# Source_OPV_ADC.net
KiCad netlist of a schematic drawn in Altium Designer
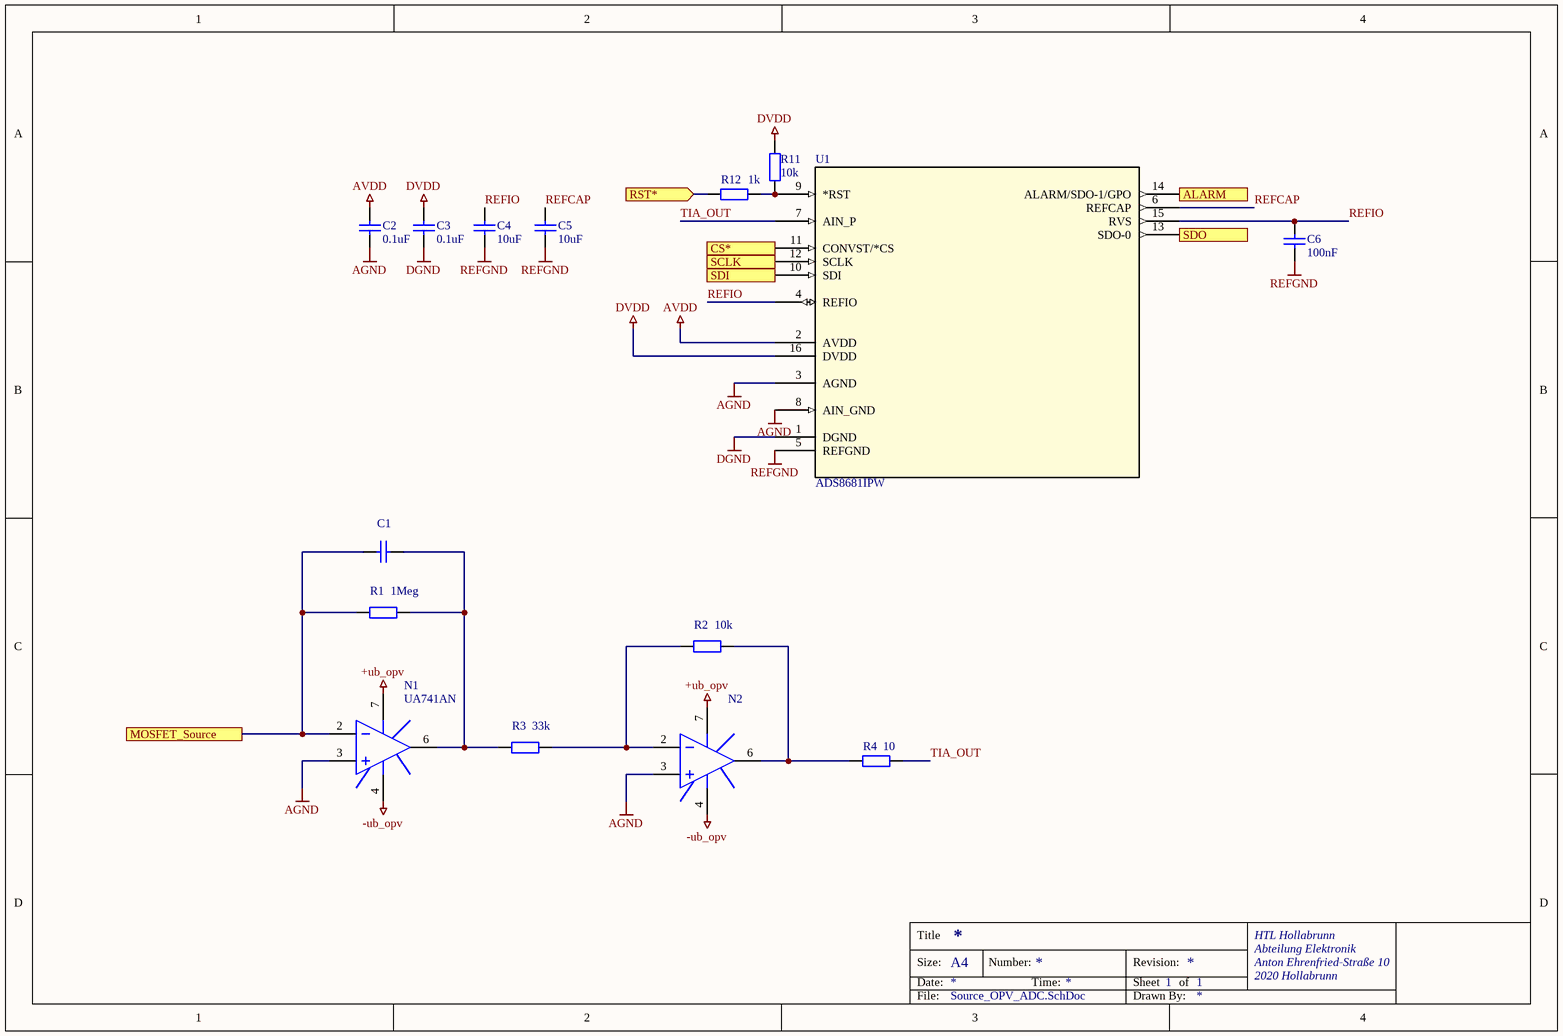
[diagram p0: Source_OPV_ADC.SchDoc]

(export (version "E")
  (design (tool "Eeschema 10.0.6"))
  (components
    (comp (ref "C1")
      (value "100nF")
      (footprint "C1206-KUE")
      (description "Capacitor")
      (fields (field (name "MANUFACTURER") "Kemet") (field (name "PUBLISHER") "Altium Limited"))
      (libsource (lib "ExtrapartsKUE_V01") (part "Capacitor"))
    )
    (comp (ref "C2")
      (value "0.1uF")
      (footprint "C1206-KUE")
      (description "Capacitor")
      (fields (field (name "MANUFACTURER") "Kemet") (field (name "PUBLISHER") "Altium Limited"))
      (libsource (lib "ExtrapartsKUE_V01") (part "Capacitor"))
    )
    (comp (ref "C3")
      (value "0.1uF")
      (footprint "C1206-KUE")
      (description "Capacitor")
      (fields (field (name "MANUFACTURER") "Kemet") (field (name "PUBLISHER") "Altium Limited"))
      (libsource (lib "ExtrapartsKUE_V01") (part "Capacitor"))
    )
    (comp (ref "C4")
      (value "10uF")
      (footprint "C1206-KUE")
      (description "Capacitor")
      (fields (field (name "MANUFACTURER") "Kemet") (field (name "PUBLISHER") "Altium Limited"))
      (libsource (lib "ExtrapartsKUE_V01") (part "Capacitor"))
    )
    (comp (ref "C5")
      (value "10uF")
      (footprint "C1206-KUE")
      (description "Capacitor")
      (fields (field (name "MANUFACTURER") "Kemet") (field (name "PUBLISHER") "Altium Limited"))
      (libsource (lib "ExtrapartsKUE_V01") (part "Capacitor"))
    )
    (comp (ref "C6")
      (value "100nF")
      (footprint "C1206-KUE")
      (description "Capacitor")
      (fields (field (name "MANUFACTURER") "Kemet") (field (name "PUBLISHER") "Altium Limited"))
      (libsource (lib "ExtrapartsKUE_V01") (part "Capacitor"))
    )
    (comp (ref "N1")
      (value "UA741AN")
      (footprint "DIP8")
      (description "General-Purpose Single Operational Amplifier")
      (fields (field (name "PUBLISHER") "Altium Limited"))
      (libsource (lib "ST Operational Amplifier") (part "UA741AN"))
    )
    (comp (ref "N2")
      (value "UA741AN")
      (footprint "DIP8")
      (description "General-Purpose Single Operational Amplifier")
      (fields (field (name "PUBLISHER") "Altium Limited"))
      (libsource (lib "ST Operational Amplifier") (part "UA741AN"))
    )
    (comp (ref "R1")
      (value "1Meg")
      (footprint "C1206-KUE")
      (description "Resistor SMD")
      (fields (field (name "MANUFACTURER") "AVX") (field (name "PUBLISHER") "Altium Limited"))
      (libsource (lib "") (part "ResistorSMD_1"))
    )
    (comp (ref "R2")
      (value "10k")
      (footprint "C1206-KUE")
      (description "Resistor SMD")
      (fields (field (name "MANUFACTURER") "AVX") (field (name "PUBLISHER") "Altium Limited"))
      (libsource (lib "") (part "ResistorSMD_1"))
    )
    (comp (ref "R3")
      (value "33k")
      (footprint "C1206-KUE")
      (description "Resistor SMD")
      (fields (field (name "MANUFACTURER") "AVX") (field (name "PUBLISHER") "Altium Limited"))
      (libsource (lib "") (part "ResistorSMD_1"))
    )
    (comp (ref "R4")
      (value "10")
      (footprint "C1206-KUE")
      (description "Resistor SMD")
      (fields (field (name "MANUFACTURER") "AVX") (field (name "PUBLISHER") "Altium Limited"))
      (libsource (lib "") (part "ResistorSMD_1"))
    )
    (comp (ref "R11")
      (value "10k")
      (footprint "C1206-KUE")
      (description "Resistor SMD")
      (fields (field (name "MANUFACTURER") "AVX") (field (name "PUBLISHER") "Altium Limited"))
      (libsource (lib "") (part "ResistorSMD_2"))
    )
    (comp (ref "R12")
      (value "1k")
      (footprint "C1206-KUE")
      (description "Resistor SMD")
      (fields (field (name "MANUFACTURER") "AVX") (field (name "PUBLISHER") "Altium Limited"))
      (libsource (lib "ExtrapartsKUE_V01") (part "ResistorSMD"))
    )
    (comp (ref "U1")
      (value "ADS8681IPW")
      (footprint "PW16_TEX")
      (fields (field (name "COPYRIGHT") "Copyright (C) 2025 Ultra Librarian. All rights reserved."))
      (libsource (lib "ADS8681IPW") (part "ADS8681IPW"))
    )
  )
  (nets
    (net (code "1") (name "+ub_opv") (class "Default")
      (node (ref "N1") (pin "7") (pinfunction "V+_7") (pintype "passive"))
      (node (ref "N2") (pin "7") (pinfunction "V+_7") (pintype "passive"))
    )
    (net (code "2") (name "-ub_opv") (class "Default")
      (node (ref "N1") (pin "4") (pinfunction "V-_4") (pintype "passive"))
      (node (ref "N2") (pin "4") (pinfunction "V-_4") (pintype "passive"))
    )
    (net (code "3") (name "/ALARM") (class "Default")
      (node (ref "U1") (pin "14") (pinfunction "ALARM/SDO-1/GPO_14") (pintype "output"))
    )
    (net (code "4") (name "/CS*") (class "Default")
      (node (ref "U1") (pin "11") (pinfunction "CONVST/*CS_11") (pintype "input"))
    )
    (net (code "5") (name "/MOSFET_Source") (class "Default")
      (node (ref "C1") (pin "1") (pinfunction "1_1") (pintype "passive"))
      (node (ref "N1") (pin "2") (pinfunction "IN-_2") (pintype "passive"))
      (node (ref "R1") (pin "2") (pinfunction "2_2") (pintype "passive"))
    )
    (net (code "6") (name "/REFCAP") (class "Default")
      (node (ref "C5") (pin "2") (pinfunction "2_2") (pintype "passive"))
      (node (ref "U1") (pin "6") (pinfunction "REFCAP_6") (pintype "output"))
    )
    (net (code "7") (name "/REFIO") (class "Default")
      (node (ref "C4") (pin "2") (pinfunction "2_2") (pintype "passive"))
      (node (ref "C6") (pin "2") (pinfunction "2_2") (pintype "passive"))
      (node (ref "U1") (pin "15") (pinfunction "RVS_15") (pintype "output"))
      (node (ref "U1") (pin "4") (pinfunction "REFIO_4") (pintype "bidirectional"))
    )
    (net (code "8") (name "/RST*") (class "Default")
      (node (ref "R12") (pin "1") (pinfunction "1_1") (pintype "passive"))
    )
    (net (code "9") (name "/SCLK") (class "Default")
      (node (ref "U1") (pin "12") (pinfunction "SCLK_12") (pintype "input"))
    )
    (net (code "10") (name "/SDI") (class "Default")
      (node (ref "U1") (pin "10") (pinfunction "SDI_10") (pintype "input"))
    )
    (net (code "11") (name "/SDO") (class "Default")
      (node (ref "U1") (pin "13") (pinfunction "SDO-0_13") (pintype "output"))
    )
    (net (code "12") (name "/TIA_OUT") (class "Default")
      (node (ref "R4") (pin "1") (pinfunction "1_1") (pintype "passive"))
      (node (ref "U1") (pin "7") (pinfunction "AIN_P_7") (pintype "input"))
    )
    (net (code "13") (name "AGND") (class "Default")
      (node (ref "C2") (pin "1") (pinfunction "1_1") (pintype "passive"))
      (node (ref "N1") (pin "3") (pinfunction "IN+_3") (pintype "passive"))
      (node (ref "N2") (pin "3") (pinfunction "IN+_3") (pintype "passive"))
      (node (ref "U1") (pin "3") (pinfunction "AGND_3") (pintype "power_in"))
      (node (ref "U1") (pin "8") (pinfunction "AIN_GND_8") (pintype "input"))
    )
    (net (code "14") (name "AVDD") (class "Default")
      (node (ref "C2") (pin "2") (pinfunction "2_2") (pintype "passive"))
      (node (ref "U1") (pin "2") (pinfunction "AVDD_2") (pintype "power_in"))
    )
    (net (code "15") (name "DGND") (class "Default")
      (node (ref "C3") (pin "1") (pinfunction "1_1") (pintype "passive"))
      (node (ref "U1") (pin "1") (pinfunction "DGND_1") (pintype "power_in"))
    )
    (net (code "16") (name "DVDD") (class "Default")
      (node (ref "C3") (pin "2") (pinfunction "2_2") (pintype "passive"))
      (node (ref "R11") (pin "1") (pinfunction "1_1") (pintype "passive"))
      (node (ref "U1") (pin "16") (pinfunction "DVDD_16") (pintype "power_in"))
    )
    (net (code "17") (name "Net-(N1-OUT)") (class "Default")
      (node (ref "C1") (pin "2") (pinfunction "2_2") (pintype "passive"))
      (node (ref "N1") (pin "6") (pinfunction "OUT_6") (pintype "passive"))
      (node (ref "R1") (pin "1") (pinfunction "1_1") (pintype "passive"))
      (node (ref "R3") (pin "2") (pinfunction "2_2") (pintype "passive"))
    )
    (net (code "18") (name "Net-(N2-IN-)") (class "Default")
      (node (ref "N2") (pin "2") (pinfunction "IN-_2") (pintype "passive"))
      (node (ref "R2") (pin "2") (pinfunction "2_2") (pintype "passive"))
      (node (ref "R3") (pin "1") (pinfunction "1_1") (pintype "passive"))
    )
    (net (code "19") (name "Net-(N2-OUT)") (class "Default")
      (node (ref "N2") (pin "6") (pinfunction "OUT_6") (pintype "passive"))
      (node (ref "R2") (pin "1") (pinfunction "1_1") (pintype "passive"))
      (node (ref "R4") (pin "2") (pinfunction "2_2") (pintype "passive"))
    )
    (net (code "20") (name "Net-(U1-*RST)") (class "Default")
      (node (ref "R11") (pin "2") (pinfunction "2_2") (pintype "passive"))
      (node (ref "R12") (pin "2") (pinfunction "2_2") (pintype "passive"))
      (node (ref "U1") (pin "9") (pinfunction "*RST_9") (pintype "input"))
    )
    (net (code "21") (name "REFGND") (class "Default")
      (node (ref "C4") (pin "1") (pinfunction "1_1") (pintype "passive"))
      (node (ref "C5") (pin "1") (pinfunction "1_1") (pintype "passive"))
      (node (ref "C6") (pin "1") (pinfunction "1_1") (pintype "passive"))
      (node (ref "U1") (pin "5") (pinfunction "REFGND_5") (pintype "power_in"))
    )
    (net (code "22") (name "unconnected-(N1-NC-Pad8)") (class "Default")
      (node (ref "N1") (pin "8") (pinfunction "NC_8") (pintype "passive"))
    )
    (net (code "23") (name "unconnected-(N1-OS_NULL-Pad1)") (class "Default")
      (node (ref "N1") (pin "1") (pinfunction "OS_NULL_1") (pintype "passive"))
    )
    (net (code "24") (name "unconnected-(N1-OS_NULL-Pad5)") (class "Default")
      (node (ref "N1") (pin "5") (pinfunction "OS_NULL_5") (pintype "passive"))
    )
    (net (code "25") (name "unconnected-(N2-NC-Pad8)") (class "Default")
      (node (ref "N2") (pin "8") (pinfunction "NC_8") (pintype "passive"))
    )
    (net (code "26") (name "unconnected-(N2-OS_NULL-Pad1)") (class "Default")
      (node (ref "N2") (pin "1") (pinfunction "OS_NULL_1") (pintype "passive"))
    )
    (net (code "27") (name "unconnected-(N2-OS_NULL-Pad5)") (class "Default")
      (node (ref "N2") (pin "5") (pinfunction "OS_NULL_5") (pintype "passive"))
    )
  )
)
